# lpc1102_revb.net
KiCad netlist of a schematic drawn in EAGLE
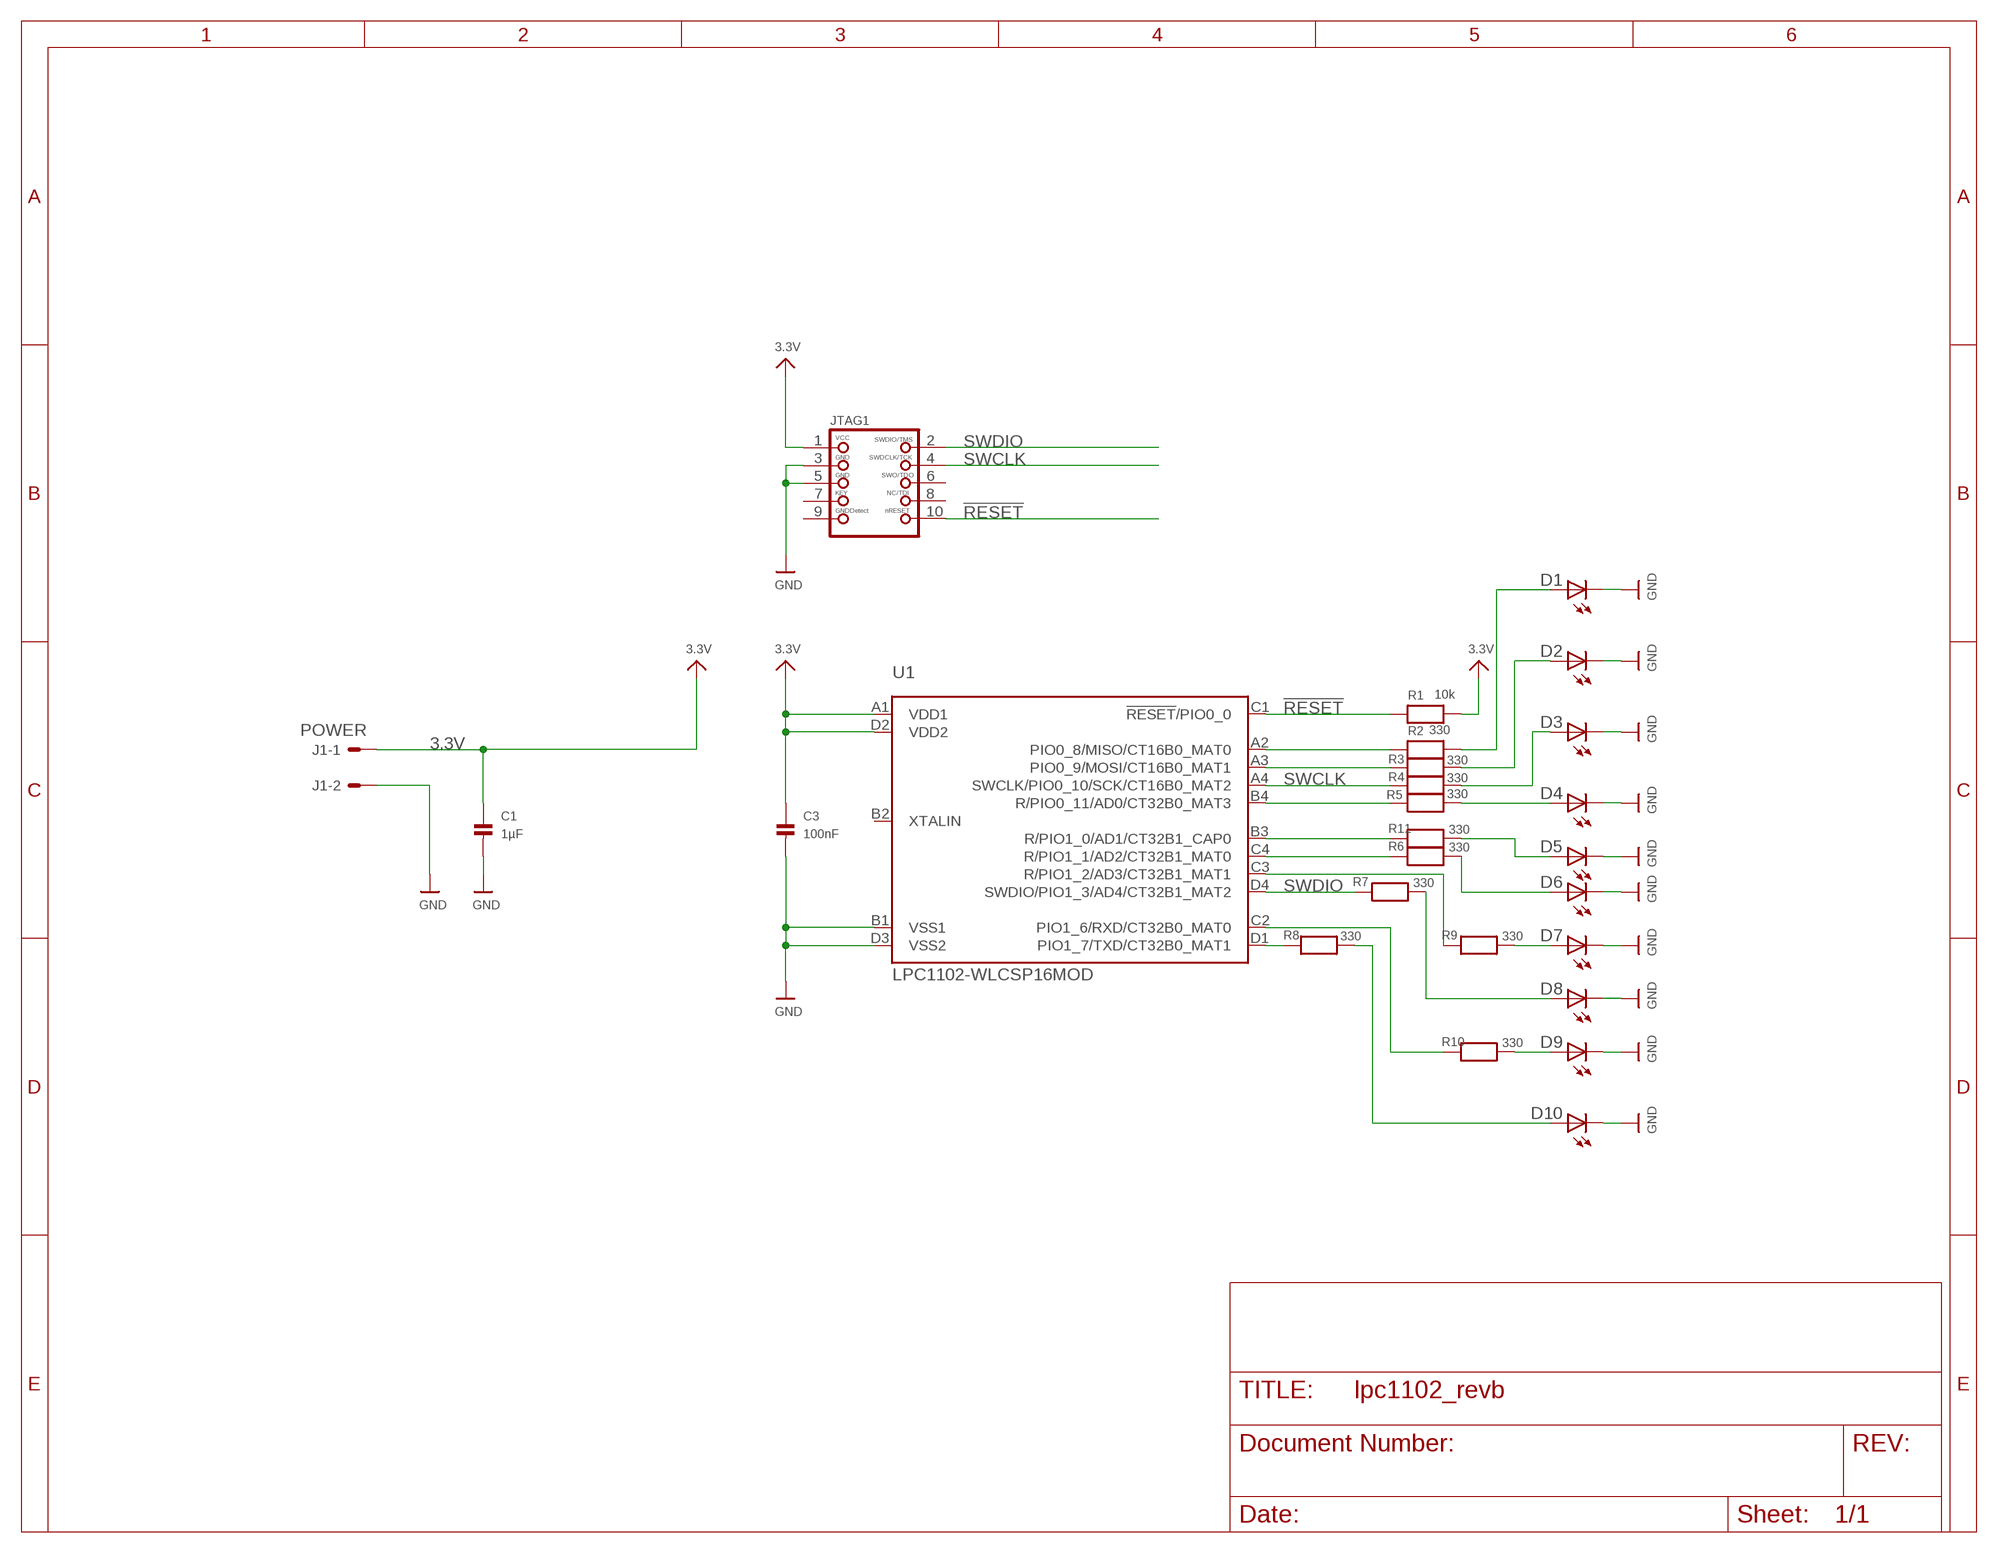
[diagram p0: schematic, sheet 1]

(export (version "E")
  (design (tool "Eeschema 10.0.6"))
  (components
    (comp (ref "C1")
      (value "1µF")
      (footprint "eagle-import:_0402")
      (libsource (lib "eagle-import") (part "CAP_CERAMIC_0402"))
    )
    (comp (ref "C3")
      (value "100nF")
      (footprint "eagle-import:_0402")
      (libsource (lib "eagle-import") (part "CAP_CERAMIC_0402"))
    )
    (comp (ref "D1")
      (value "LEDCHIP-LED0603")
      (footprint "eagle-import:CHIP-LED0603")
      (libsource (lib "eagle-import") (part "LEDCHIP-LED0603"))
    )
    (comp (ref "D2")
      (value "LEDCHIP-LED0603")
      (footprint "eagle-import:CHIP-LED0603")
      (libsource (lib "eagle-import") (part "LEDCHIP-LED0603"))
    )
    (comp (ref "D3")
      (value "LEDCHIP-LED0603")
      (footprint "eagle-import:CHIP-LED0603")
      (libsource (lib "eagle-import") (part "LEDCHIP-LED0603"))
    )
    (comp (ref "D4")
      (value "LEDCHIP-LED0603")
      (footprint "eagle-import:CHIP-LED0603")
      (libsource (lib "eagle-import") (part "LEDCHIP-LED0603"))
    )
    (comp (ref "D5")
      (value "LEDCHIP-LED0603")
      (footprint "eagle-import:CHIP-LED0603")
      (libsource (lib "eagle-import") (part "LEDCHIP-LED0603"))
    )
    (comp (ref "D6")
      (value "LEDCHIP-LED0603")
      (footprint "eagle-import:CHIP-LED0603")
      (libsource (lib "eagle-import") (part "LEDCHIP-LED0603"))
    )
    (comp (ref "D7")
      (value "LEDCHIP-LED0603")
      (footprint "eagle-import:CHIP-LED0603")
      (libsource (lib "eagle-import") (part "LEDCHIP-LED0603"))
    )
    (comp (ref "D8")
      (value "LEDCHIP-LED0603")
      (footprint "eagle-import:CHIP-LED0603")
      (libsource (lib "eagle-import") (part "LEDCHIP-LED0603"))
    )
    (comp (ref "D9")
      (value "LEDCHIP-LED0603")
      (footprint "eagle-import:CHIP-LED0603")
      (libsource (lib "eagle-import") (part "LEDCHIP-LED0603"))
    )
    (comp (ref "D10")
      (value "LEDCHIP-LED0603")
      (footprint "eagle-import:CHIP-LED0603")
      (libsource (lib "eagle-import") (part "LEDCHIP-LED0603"))
    )
    (comp (ref "J1")
      (value "POWER")
      (footprint "eagle-import:6410-02")
      (libsource (lib "eagle-import") (part "22-?-0227-2021"))
    )
    (comp (ref "JTAG1")
      (value "JTAG-CORTEXM3SMT")
      (footprint "eagle-import:2X05_1.27MM_SMT")
      (libsource (lib "eagle-import") (part "JTAG-CORTEXM3SMT"))
    )
    (comp (ref "R1")
      (value "10k")
      (footprint "eagle-import:_0402")
      (libsource (lib "eagle-import") (part "RESISTOR_0402"))
    )
    (comp (ref "R2")
      (value "330")
      (footprint "eagle-import:_0402")
      (libsource (lib "eagle-import") (part "RESISTOR_0402"))
    )
    (comp (ref "R3")
      (value "330")
      (footprint "eagle-import:_0402")
      (libsource (lib "eagle-import") (part "RESISTOR_0402"))
    )
    (comp (ref "R4")
      (value "330")
      (footprint "eagle-import:_0402")
      (libsource (lib "eagle-import") (part "RESISTOR_0402"))
    )
    (comp (ref "R5")
      (value "330")
      (footprint "eagle-import:_0402")
      (libsource (lib "eagle-import") (part "RESISTOR_0402"))
    )
    (comp (ref "R6")
      (value "330")
      (footprint "eagle-import:_0402")
      (libsource (lib "eagle-import") (part "RESISTOR_0402"))
    )
    (comp (ref "R7")
      (value "330")
      (footprint "eagle-import:_0402")
      (libsource (lib "eagle-import") (part "RESISTOR_0402"))
    )
    (comp (ref "R8")
      (value "330")
      (footprint "eagle-import:_0402")
      (libsource (lib "eagle-import") (part "RESISTOR_0402"))
    )
    (comp (ref "R9")
      (value "330")
      (footprint "eagle-import:_0402")
      (libsource (lib "eagle-import") (part "RESISTOR_0402"))
    )
    (comp (ref "R10")
      (value "330")
      (footprint "eagle-import:_0402")
      (libsource (lib "eagle-import") (part "RESISTOR_0402"))
    )
    (comp (ref "R11")
      (value "330")
      (footprint "eagle-import:_0402")
      (libsource (lib "eagle-import") (part "RESISTOR_0402"))
    )
    (comp (ref "U1")
      (value "LPC1102-WLCSP16MOD")
      (footprint "eagle-import:WLCSP16_MOD")
      (libsource (lib "eagle-import") (part "LPC1102-WLCSP16MOD"))
    )
  )
  (nets
    (net (code "1") (name "/SWCLK") (class "Default")
      (node (ref "JTAG1") (pin "4") (pinfunction "4_4") (pintype "passive"))
      (node (ref "R4") (pin "1") (pinfunction "1_1") (pintype "passive"))
      (node (ref "U1") (pin "A4") (pinfunction "SWCLK/PIO0_10/SCK/CT16B0_MAT2_A4") (pintype "bidirectional"))
    )
    (net (code "2") (name "/SWDIO") (class "Default")
      (node (ref "JTAG1") (pin "2") (pinfunction "2_2") (pintype "passive"))
      (node (ref "R7") (pin "1") (pinfunction "1_1") (pintype "passive"))
      (node (ref "U1") (pin "D4") (pinfunction "SWDIO/PIO1_3/AD4/CT32B1_MAT2_D4") (pintype "bidirectional"))
    )
    (net (code "3") (name "/~{RESET}") (class "Default")
      (node (ref "JTAG1") (pin "10") (pinfunction "10_10") (pintype "passive"))
      (node (ref "R1") (pin "1") (pinfunction "1_1") (pintype "passive"))
      (node (ref "U1") (pin "C1") (pinfunction "~{RESET}/PIO0_0_C1") (pintype "bidirectional"))
    )
    (net (code "4") (name "3.3V") (class "Default")
      (node (ref "C1") (pin "1") (pinfunction "P$1_1") (pintype "passive"))
      (node (ref "C3") (pin "1") (pinfunction "P$1_1") (pintype "passive"))
      (node (ref "J1") (pin "1") (pinfunction "S_1") (pintype "passive"))
      (node (ref "JTAG1") (pin "1") (pinfunction "1_1") (pintype "passive"))
      (node (ref "R1") (pin "2") (pinfunction "2_2") (pintype "passive"))
      (node (ref "U1") (pin "A1") (pinfunction "VDD1_A1") (pintype "power_in"))
      (node (ref "U1") (pin "D2") (pinfunction "VDD2_D2") (pintype "power_in"))
    )
    (net (code "5") (name "GND") (class "Default")
      (node (ref "C1") (pin "2") (pinfunction "P$2_2") (pintype "passive"))
      (node (ref "C3") (pin "2") (pinfunction "P$2_2") (pintype "passive"))
      (node (ref "D1") (pin "C") (pinfunction "C_C") (pintype "passive"))
      (node (ref "D10") (pin "C") (pinfunction "C_C") (pintype "passive"))
      (node (ref "D2") (pin "C") (pinfunction "C_C") (pintype "passive"))
      (node (ref "D3") (pin "C") (pinfunction "C_C") (pintype "passive"))
      (node (ref "D4") (pin "C") (pinfunction "C_C") (pintype "passive"))
      (node (ref "D5") (pin "C") (pinfunction "C_C") (pintype "passive"))
      (node (ref "D6") (pin "C") (pinfunction "C_C") (pintype "passive"))
      (node (ref "D7") (pin "C") (pinfunction "C_C") (pintype "passive"))
      (node (ref "D8") (pin "C") (pinfunction "C_C") (pintype "passive"))
      (node (ref "D9") (pin "C") (pinfunction "C_C") (pintype "passive"))
      (node (ref "J1") (pin "2") (pinfunction "S_2") (pintype "passive"))
      (node (ref "JTAG1") (pin "3") (pinfunction "3_3") (pintype "passive"))
      (node (ref "JTAG1") (pin "5") (pinfunction "5_5") (pintype "passive"))
      (node (ref "U1") (pin "B1") (pinfunction "VSS1_B1") (pintype "power_in"))
      (node (ref "U1") (pin "D3") (pinfunction "VSS2_D3") (pintype "power_in"))
    )
    (net (code "6") (name "Net-(D1-PadA)") (class "Default")
      (node (ref "D1") (pin "A") (pinfunction "A_A") (pintype "passive"))
      (node (ref "R2") (pin "2") (pinfunction "2_2") (pintype "passive"))
    )
    (net (code "7") (name "Net-(D2-PadA)") (class "Default")
      (node (ref "D2") (pin "A") (pinfunction "A_A") (pintype "passive"))
      (node (ref "R3") (pin "2") (pinfunction "2_2") (pintype "passive"))
    )
    (net (code "8") (name "Net-(D3-PadA)") (class "Default")
      (node (ref "D3") (pin "A") (pinfunction "A_A") (pintype "passive"))
      (node (ref "R4") (pin "2") (pinfunction "2_2") (pintype "passive"))
    )
    (net (code "9") (name "Net-(D4-PadA)") (class "Default")
      (node (ref "D4") (pin "A") (pinfunction "A_A") (pintype "passive"))
      (node (ref "R5") (pin "2") (pinfunction "2_2") (pintype "passive"))
    )
    (net (code "10") (name "Net-(D5-PadA)") (class "Default")
      (node (ref "D5") (pin "A") (pinfunction "A_A") (pintype "passive"))
      (node (ref "R11") (pin "2") (pinfunction "2_2") (pintype "passive"))
    )
    (net (code "11") (name "Net-(D6-PadA)") (class "Default")
      (node (ref "D6") (pin "A") (pinfunction "A_A") (pintype "passive"))
      (node (ref "R6") (pin "2") (pinfunction "2_2") (pintype "passive"))
    )
    (net (code "12") (name "Net-(D7-PadA)") (class "Default")
      (node (ref "D7") (pin "A") (pinfunction "A_A") (pintype "passive"))
      (node (ref "R9") (pin "2") (pinfunction "2_2") (pintype "passive"))
    )
    (net (code "13") (name "Net-(D8-PadA)") (class "Default")
      (node (ref "D8") (pin "A") (pinfunction "A_A") (pintype "passive"))
      (node (ref "R7") (pin "2") (pinfunction "2_2") (pintype "passive"))
    )
    (net (code "14") (name "Net-(D9-PadA)") (class "Default")
      (node (ref "D9") (pin "A") (pinfunction "A_A") (pintype "passive"))
      (node (ref "R10") (pin "2") (pinfunction "2_2") (pintype "passive"))
    )
    (net (code "15") (name "Net-(D10-PadA)") (class "Default")
      (node (ref "D10") (pin "A") (pinfunction "A_A") (pintype "passive"))
      (node (ref "R8") (pin "2") (pinfunction "2_2") (pintype "passive"))
    )
    (net (code "16") (name "Net-(U1-PIO0_8{slash}MISO{slash}CT16B0_MAT0)") (class "Default")
      (node (ref "R2") (pin "1") (pinfunction "1_1") (pintype "passive"))
      (node (ref "U1") (pin "A2") (pinfunction "PIO0_8/MISO/CT16B0_MAT0_A2") (pintype "bidirectional"))
    )
    (net (code "17") (name "Net-(U1-PIO0_9{slash}MOSI{slash}CT16B0_MAT1)") (class "Default")
      (node (ref "R3") (pin "1") (pinfunction "1_1") (pintype "passive"))
      (node (ref "U1") (pin "A3") (pinfunction "PIO0_9/MOSI/CT16B0_MAT1_A3") (pintype "bidirectional"))
    )
    (net (code "18") (name "Net-(U1-PIO1_6{slash}RXD{slash}CT32B0_MAT0)") (class "Default")
      (node (ref "R10") (pin "1") (pinfunction "1_1") (pintype "passive"))
      (node (ref "U1") (pin "C2") (pinfunction "PIO1_6/RXD/CT32B0_MAT0_C2") (pintype "bidirectional"))
    )
    (net (code "19") (name "Net-(U1-PIO1_7{slash}TXD{slash}CT32B0_MAT1)") (class "Default")
      (node (ref "R8") (pin "1") (pinfunction "1_1") (pintype "passive"))
      (node (ref "U1") (pin "D1") (pinfunction "PIO1_7/TXD/CT32B0_MAT1_D1") (pintype "bidirectional"))
    )
    (net (code "20") (name "Net-(U1-R{slash}PIO0_11{slash}AD0{slash}CT32B0_MAT3)") (class "Default")
      (node (ref "R5") (pin "1") (pinfunction "1_1") (pintype "passive"))
      (node (ref "U1") (pin "B4") (pinfunction "R/PIO0_11/AD0/CT32B0_MAT3_B4") (pintype "bidirectional"))
    )
    (net (code "21") (name "Net-(U1-R{slash}PIO1_0{slash}AD1{slash}CT32B1_CAP0)") (class "Default")
      (node (ref "R11") (pin "1") (pinfunction "1_1") (pintype "passive"))
      (node (ref "U1") (pin "B3") (pinfunction "R/PIO1_0/AD1/CT32B1_CAP0_B3") (pintype "bidirectional"))
    )
    (net (code "22") (name "Net-(U1-R{slash}PIO1_1{slash}AD2{slash}CT32B1_MAT0)") (class "Default")
      (node (ref "R6") (pin "1") (pinfunction "1_1") (pintype "passive"))
      (node (ref "U1") (pin "C4") (pinfunction "R/PIO1_1/AD2/CT32B1_MAT0_C4") (pintype "bidirectional"))
    )
    (net (code "23") (name "Net-(U1-R{slash}PIO1_2{slash}AD3{slash}CT32B1_MAT1)") (class "Default")
      (node (ref "R9") (pin "1") (pinfunction "1_1") (pintype "passive"))
      (node (ref "U1") (pin "C3") (pinfunction "R/PIO1_2/AD3/CT32B1_MAT1_C3") (pintype "bidirectional"))
    )
    (net (code "24") (name "unconnected-(JTAG1-Pad6)") (class "Default")
      (node (ref "JTAG1") (pin "6") (pinfunction "6_6") (pintype "passive"))
    )
    (net (code "25") (name "unconnected-(JTAG1-Pad7)") (class "Default")
      (node (ref "JTAG1") (pin "7") (pinfunction "7_7") (pintype "passive"))
    )
    (net (code "26") (name "unconnected-(JTAG1-Pad8)") (class "Default")
      (node (ref "JTAG1") (pin "8") (pinfunction "8_8") (pintype "passive"))
    )
    (net (code "27") (name "unconnected-(JTAG1-Pad9)") (class "Default")
      (node (ref "JTAG1") (pin "9") (pinfunction "9_9") (pintype "passive"))
    )
    (net (code "28") (name "unconnected-(U1-XTALIN-PadB2)") (class "Default")
      (node (ref "U1") (pin "B2") (pinfunction "XTALIN_B2") (pintype "passive"))
    )
  )
)
